# Display.net
KiCad netlist of a schematic drawn in Altium Designer
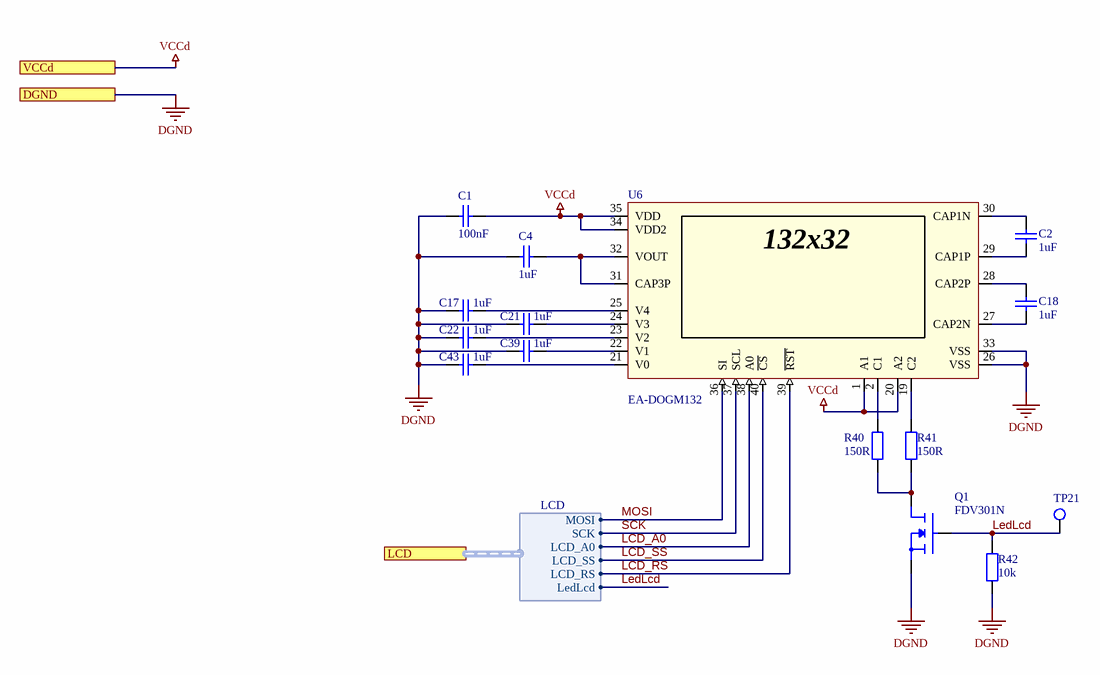
[diagram p0: Display.SchDoc]

(export (version "E")
  (design (tool "Eeschema 10.0.6"))
  (components
    (comp (ref "C1")
      (value "100nF")
      (footprint "CAPC2012N")
      (description "Capacitor")
      (libsource (lib "Balance") (part "Cap_100nF"))
    )
    (comp (ref "C2")
      (value "1uF")
      (footprint "CAPC2012N")
      (description "Capacitor")
      (libsource (lib "Balance") (part "Cap_1uF"))
    )
    (comp (ref "C4")
      (value "1uF")
      (footprint "CAPC2012N")
      (description "Capacitor")
      (libsource (lib "Balance") (part "Cap_1uF"))
    )
    (comp (ref "C17")
      (value "1uF")
      (footprint "CAPC2012N")
      (description "Capacitor")
      (libsource (lib "Balance") (part "Cap_1uF"))
    )
    (comp (ref "C18")
      (value "1uF")
      (footprint "CAPC2012N")
      (description "Capacitor")
      (libsource (lib "Balance") (part "Cap_1uF"))
    )
    (comp (ref "C21")
      (value "1uF")
      (footprint "CAPC2012N")
      (description "Capacitor")
      (libsource (lib "Balance") (part "Cap_1uF"))
    )
    (comp (ref "C22")
      (value "1uF")
      (footprint "CAPC2012N")
      (description "Capacitor")
      (libsource (lib "Balance") (part "Cap_1uF"))
    )
    (comp (ref "C39")
      (value "1uF")
      (footprint "CAPC2012N")
      (description "Capacitor")
      (libsource (lib "Balance") (part "Cap_1uF"))
    )
    (comp (ref "C43")
      (value "1uF")
      (footprint "CAPC2012N")
      (description "Capacitor")
      (libsource (lib "Balance") (part "Cap_1uF"))
    )
    (comp (ref "Q1") (value "FDV301N") (footprint "SOT23-3N") (libsource (lib "Balance") (part "FDV301N")))
    (comp (ref "R40")
      (value "150R")
      (footprint "RESC2012N")
      (description "Resistor")
      (libsource (lib "Balance") (part "Res_150R"))
    )
    (comp (ref "R41")
      (value "150R")
      (footprint "RESC2012N")
      (description "Resistor")
      (libsource (lib "Balance") (part "Res_150R"))
    )
    (comp (ref "R42")
      (value "10k")
      (footprint "RESC2012N")
      (description "Resistor")
      (libsource (lib "Balance") (part "Res_10k"))
    )
    (comp (ref "TP21")
      (value "TP")
      (footprint "Testpoint")
      (description "=Value")
      (libsource (lib "Balance") (part "TP"))
    )
    (comp (ref "U6")
      (value "EA-DOGM132")
      (footprint "EA_DOGM132_WITH_BACKLIGHT")
      (description "Chip On Glass Graphic LCD")
      (libsource (lib "Balance") (part "DOGM_132-5"))
    )
  )
  (nets
    (net (code "2") (name "/LCD_A0") (class "Default")
      (node (ref "U6") (pin "38") (pinfunction "A0_38") (pintype "input"))
    )
    (net (code "3") (name "/LCD_RS") (class "Default")
      (node (ref "U6") (pin "39") (pinfunction "RST_39") (pintype "input"))
    )
    (net (code "4") (name "/LCD_SS") (class "Default")
      (node (ref "U6") (pin "40") (pinfunction "CS_40") (pintype "input"))
    )
    (net (code "5") (name "/LedLcd") (class "Default")
      (node (ref "Q1") (pin "1") (pinfunction "G_1") (pintype "passive"))
      (node (ref "R42") (pin "2") (pinfunction "2_2") (pintype "passive"))
      (node (ref "TP21") (pin "1") (pinfunction "1_1") (pintype "passive"))
    )
    (net (code "6") (name "/MOSI") (class "Default")
      (node (ref "U6") (pin "36") (pinfunction "SI_36") (pintype "input"))
    )
    (net (code "7") (name "/SCK") (class "Default")
      (node (ref "U6") (pin "37") (pinfunction "SCL_37") (pintype "input"))
    )
    (net (code "9") (name "DGND") (class "Default")
      (node (ref "C1") (pin "1") (pinfunction "1_1") (pintype "passive"))
      (node (ref "C17") (pin "1") (pinfunction "1_1") (pintype "passive"))
      (node (ref "C21") (pin "1") (pinfunction "1_1") (pintype "passive"))
      (node (ref "C22") (pin "1") (pinfunction "1_1") (pintype "passive"))
      (node (ref "C39") (pin "1") (pinfunction "1_1") (pintype "passive"))
      (node (ref "C4") (pin "1") (pinfunction "1_1") (pintype "passive"))
      (node (ref "C43") (pin "1") (pinfunction "1_1") (pintype "passive"))
      (node (ref "Q1") (pin "2") (pinfunction "S_2") (pintype "passive"))
      (node (ref "R42") (pin "1") (pinfunction "1_1") (pintype "passive"))
      (node (ref "U6") (pin "26") (pinfunction "VSS_26") (pintype "power_in"))
      (node (ref "U6") (pin "33") (pinfunction "VSS_33") (pintype "power_in"))
    )
    (net (code "10") (name "Net-(Q1-D)") (class "Default")
      (node (ref "Q1") (pin "3") (pinfunction "D_3") (pintype "passive"))
      (node (ref "R40") (pin "1") (pinfunction "1_1") (pintype "passive"))
      (node (ref "R41") (pin "1") (pinfunction "1_1") (pintype "passive"))
    )
    (net (code "11") (name "Net-(U6-C1)") (class "Default")
      (node (ref "R40") (pin "2") (pinfunction "2_2") (pintype "passive"))
      (node (ref "U6") (pin "2") (pinfunction "C1_2") (pintype "passive"))
    )
    (net (code "12") (name "Net-(U6-C2)") (class "Default")
      (node (ref "R41") (pin "2") (pinfunction "2_2") (pintype "passive"))
      (node (ref "U6") (pin "19") (pinfunction "C2_19") (pintype "passive"))
    )
    (net (code "13") (name "Net-(U6-CAP1N)") (class "Default")
      (node (ref "C2") (pin "2") (pinfunction "2_2") (pintype "passive"))
      (node (ref "U6") (pin "30") (pinfunction "CAP1N_30") (pintype "passive"))
    )
    (net (code "14") (name "Net-(U6-CAP1P)") (class "Default")
      (node (ref "C2") (pin "1") (pinfunction "1_1") (pintype "passive"))
      (node (ref "U6") (pin "29") (pinfunction "CAP1P_29") (pintype "passive"))
    )
    (net (code "15") (name "Net-(U6-CAP2N)") (class "Default")
      (node (ref "C18") (pin "1") (pinfunction "1_1") (pintype "passive"))
      (node (ref "U6") (pin "27") (pinfunction "CAP2N_27") (pintype "passive"))
    )
    (net (code "16") (name "Net-(U6-CAP2P)") (class "Default")
      (node (ref "C18") (pin "2") (pinfunction "2_2") (pintype "passive"))
      (node (ref "U6") (pin "28") (pinfunction "CAP2P_28") (pintype "passive"))
    )
    (net (code "17") (name "Net-(U6-CAP3P)") (class "Default")
      (node (ref "C4") (pin "2") (pinfunction "2_2") (pintype "passive"))
      (node (ref "U6") (pin "31") (pinfunction "CAP3P_31") (pintype "passive"))
      (node (ref "U6") (pin "32") (pinfunction "VOUT_32") (pintype "passive"))
    )
    (net (code "18") (name "Net-(U6-V0)") (class "Default")
      (node (ref "C43") (pin "2") (pinfunction "2_2") (pintype "passive"))
      (node (ref "U6") (pin "21") (pinfunction "V0_21") (pintype "passive"))
    )
    (net (code "19") (name "Net-(U6-V1)") (class "Default")
      (node (ref "C39") (pin "2") (pinfunction "2_2") (pintype "passive"))
      (node (ref "U6") (pin "22") (pinfunction "V1_22") (pintype "passive"))
    )
    (net (code "20") (name "Net-(U6-V2)") (class "Default")
      (node (ref "C22") (pin "2") (pinfunction "2_2") (pintype "passive"))
      (node (ref "U6") (pin "23") (pinfunction "V2_23") (pintype "passive"))
    )
    (net (code "21") (name "Net-(U6-V3)") (class "Default")
      (node (ref "C21") (pin "2") (pinfunction "2_2") (pintype "passive"))
      (node (ref "U6") (pin "24") (pinfunction "V3_24") (pintype "passive"))
    )
    (net (code "22") (name "Net-(U6-V4)") (class "Default")
      (node (ref "C17") (pin "2") (pinfunction "2_2") (pintype "passive"))
      (node (ref "U6") (pin "25") (pinfunction "V4_25") (pintype "passive"))
    )
    (net (code "23") (name "VCCd") (class "Default")
      (node (ref "C1") (pin "2") (pinfunction "2_2") (pintype "passive"))
      (node (ref "U6") (pin "1") (pinfunction "A1_1") (pintype "passive"))
      (node (ref "U6") (pin "20") (pinfunction "A2_20") (pintype "passive"))
      (node (ref "U6") (pin "34") (pinfunction "VDD2_34") (pintype "power_in"))
      (node (ref "U6") (pin "35") (pinfunction "VDD_35") (pintype "power_in"))
    )
  )
)
